# UART_RS485.net
KiCad netlist of a schematic drawn in Altium Designer
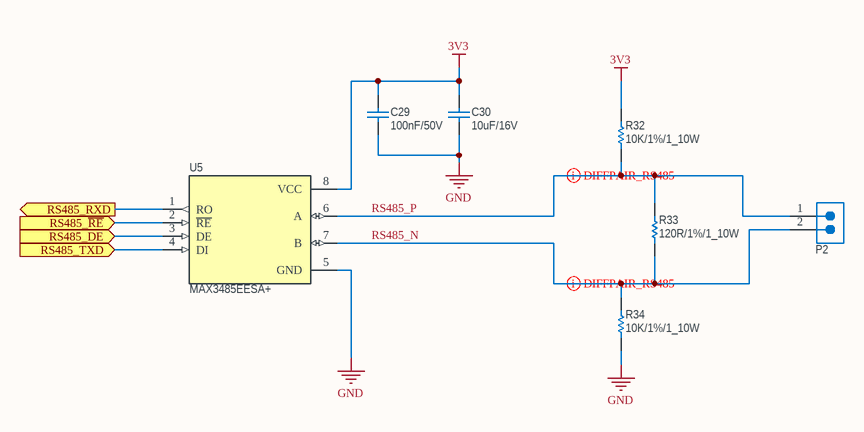
[diagram p0: UART_RS485.SchDoc]

(export (version "E")
  (design (tool "Eeschema 10.0.6"))
  (components
    (comp (ref "C29")
      (value "100nF/50V")
      (footprint "CAP_0603")
      (description "CAP, size 0603, 100nF, 50V")
      (fields (field (name "SUPPLY PART NUMBER") "Tụ Gốm 0603 100nF (0.1uF) 50V"))
      (libsource (lib "BluetoothTracking") (part "Ceramic_Cap_100nF_50V_0603"))
    )
    (comp (ref "C30")
      (value "10uF/16V")
      (footprint "CAP_0603")
      (description "CAP, size 0603, 10uF, 16V")
      (fields (field (name "SUPPLY PART NUMBER") "Tụ Gốm 0603 10uF 16V"))
      (libsource (lib "BluetoothTracking") (part "Ceramic_Cap_10uF_16V_0603"))
    )
    (comp (ref "P2")
      (value "3.81mm_2P")
      (footprint "Terminal_Block_3.81mm_2P")
      (description "Terminal Block THT, pitch 3.81mm, 2p, 300V, 10A")
      (fields
        (field (name "SUPPLY PART NUMBER") "UL-3.81-2-R Terminal Block Plug-in Hàn PCB 2 Chân Cong 3.81mm 300V 10A ULO")
      )
      (libsource (lib "BluetoothTracking") (part "Terminal_Block_3.81mm_2P"))
    )
    (comp (ref "R32")
      (value "10K/1%/1_10W")
      (footprint "Resistor_0603")
      (description "Resistor 0603 10KOhm 1% 1_10W")
      (fields (field (name "SUPPLY PART NUMBER") "Điện Trở 10 KOhm 0603 1%"))
      (libsource (lib "BluetoothTracking") (part "Res_10K_0603_1%"))
    )
    (comp (ref "R33")
      (value "120R/1%/1_10W")
      (footprint "Resistor_0603")
      (description "Resistor 0603 120 Ohm 1% 1_10W")
      (fields (field (name "SUPPLY PART NUMBER") "Điện Trở 120 Ohm 0603 1%"))
      (libsource (lib "BluetoothTracking") (part "Res_120R_0603_1%"))
    )
    (comp (ref "R34")
      (value "10K/1%/1_10W")
      (footprint "Resistor_0603")
      (description "Resistor 0603 10KOhm 1% 1_10W")
      (fields (field (name "SUPPLY PART NUMBER") "Điện Trở 10 KOhm 0603 1%"))
      (libsource (lib "BluetoothTracking") (part "Res_10K_0603_1%"))
    )
    (comp (ref "U5")
      (value "MAX3485EESA+")
      (footprint "SOIC-8")
      (description "1/1 Transceiver Half RS422, RS485 8-SOIC")
      (fields (field (name "SUPPLY PART NUMBER") "MAX3485EESA+ Line Transceiver, 8-SOIC"))
      (libsource (lib "BluetoothTracking") (part "MAX3485EESA+"))
    )
  )
  (nets
    (net (code "1") (name "/RS485_DE") (class "Default")
      (node (ref "U5") (pin "3") (pinfunction "DE_3") (pintype "input"))
    )
    (net (code "2") (name "/RS485_N") (class "Default")
      (node (ref "P2") (pin "2") (pinfunction "2_2") (pintype "passive"))
      (node (ref "R33") (pin "1") (pinfunction "1_1") (pintype "passive"))
      (node (ref "R34") (pin "1") (pinfunction "1_1") (pintype "passive"))
      (node (ref "U5") (pin "7") (pinfunction "B_7") (pintype "bidirectional"))
    )
    (net (code "3") (name "/RS485_P") (class "Default")
      (node (ref "P2") (pin "1") (pinfunction "1_1") (pintype "passive"))
      (node (ref "R32") (pin "1") (pinfunction "1_1") (pintype "passive"))
      (node (ref "R33") (pin "2") (pinfunction "2_2") (pintype "passive"))
      (node (ref "U5") (pin "6") (pinfunction "A_6") (pintype "bidirectional"))
    )
    (net (code "4") (name "/RS485_RXD") (class "Default")
      (node (ref "U5") (pin "1") (pinfunction "RO_1") (pintype "output"))
    )
    (net (code "5") (name "/RS485_TXD") (class "Default")
      (node (ref "U5") (pin "4") (pinfunction "DI_4") (pintype "input"))
    )
    (net (code "6") (name "/RS485_~{RE}") (class "Default")
      (node (ref "U5") (pin "2") (pinfunction "~{RE}_2") (pintype "input"))
    )
    (net (code "7") (name "3V3") (class "Default")
      (node (ref "C29") (pin "2") (pinfunction "2_2") (pintype "passive"))
      (node (ref "C30") (pin "2") (pinfunction "2_2") (pintype "passive"))
      (node (ref "R32") (pin "2") (pinfunction "2_2") (pintype "passive"))
      (node (ref "U5") (pin "8") (pinfunction "VCC_8") (pintype "power_in"))
    )
    (net (code "8") (name "GND") (class "Default")
      (node (ref "C29") (pin "1") (pinfunction "1_1") (pintype "passive"))
      (node (ref "C30") (pin "1") (pinfunction "1_1") (pintype "passive"))
      (node (ref "R34") (pin "2") (pinfunction "2_2") (pintype "passive"))
      (node (ref "U5") (pin "5") (pinfunction "GND_5") (pintype "power_in"))
    )
  )
)
